# GPS_module.net
KiCad netlist of a schematic drawn in EAGLE
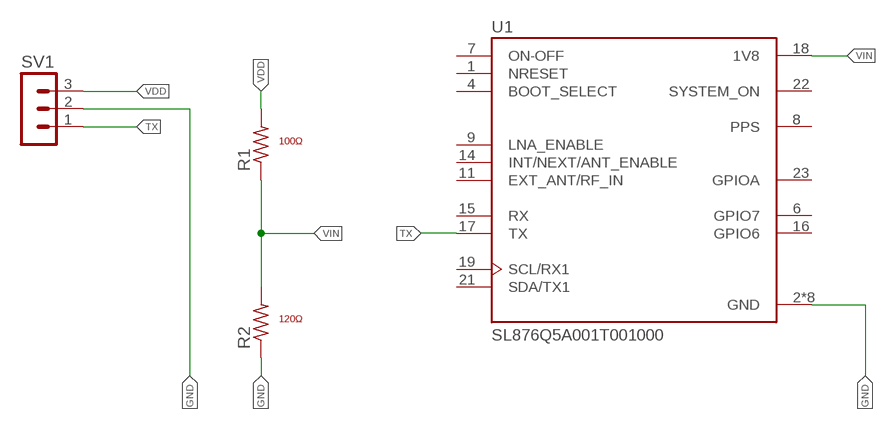
[diagram p0: schematic, sheet 1]

(export (version "E")
  (design (tool "Eeschema 10.0.6"))
  (components
    (comp (ref "R1")
      (value "100")
      (footprint "eagle-import:RESC2012X65N")
      (fields
        (field (name "COMMENT") "1623401-1")
        (field (name "MF") "TE Connectivity")
        (field (name "TOLERANCE") "0%")
      )
      (libsource (lib "eagle-import") (part "1623401-1"))
    )
    (comp (ref "R2")
      (value "120")
      (footprint "eagle-import:RESC2012X65N")
      (fields
        (field (name "COMMENT") "1623401-1")
        (field (name "MF") "TE Connectivity")
        (field (name "TOLERANCE") "0%")
      )
      (libsource (lib "eagle-import") (part "1623401-1"))
    )
    (comp (ref "SV1")
      (value "MA03-1")
      (footprint "eagle-import:MA03-1")
      (libsource (lib "eagle-import") (part "MA03-1"))
    )
    (comp (ref "U1")
      (value "SL876Q5A001T001000")
      (footprint "eagle-import:XCVR_SL876Q5A001T001000")
      (fields (field (name "MF") "Telit"))
      (libsource (lib "eagle-import") (part "SL876Q5A001T001000"))
    )
  )
  (nets
    (net (code "1") (name "GND") (class "Default")
      (node (ref "R2") (pin "1") (pinfunction "1_1") (pintype "passive"))
      (node (ref "SV1") (pin "2") (pinfunction "2_2") (pintype "passive"))
      (node (ref "U1") (pin "10") (pinfunction "GND_10") (pintype "power_in"))
      (node (ref "U1") (pin "12") (pinfunction "GND_12") (pintype "power_in"))
      (node (ref "U1") (pin "13") (pinfunction "GND_13") (pintype "power_in"))
      (node (ref "U1") (pin "2") (pinfunction "GND_2") (pintype "power_in"))
      (node (ref "U1") (pin "20") (pinfunction "GND_20") (pintype "power_in"))
      (node (ref "U1") (pin "24") (pinfunction "GND_24") (pintype "power_in"))
      (node (ref "U1") (pin "3") (pinfunction "GND_3") (pintype "power_in"))
      (node (ref "U1") (pin "5") (pinfunction "GND_5") (pintype "power_in"))
    )
    (net (code "2") (name "TX") (class "Default")
      (node (ref "SV1") (pin "1") (pinfunction "1_1") (pintype "passive"))
      (node (ref "U1") (pin "17") (pinfunction "TX_17") (pintype "output"))
    )
    (net (code "3") (name "VDD") (class "Default")
      (node (ref "R1") (pin "2") (pinfunction "2_2") (pintype "passive"))
      (node (ref "SV1") (pin "3") (pinfunction "3_3") (pintype "passive"))
    )
    (net (code "4") (name "VIN") (class "Default")
      (node (ref "R1") (pin "1") (pinfunction "1_1") (pintype "passive"))
      (node (ref "R2") (pin "2") (pinfunction "2_2") (pintype "passive"))
      (node (ref "U1") (pin "18") (pinfunction "1V8_18") (pintype "power_in"))
    )
    (net (code "5") (name "unconnected-(U1-BOOT_SELECT-Pad4)") (class "Default")
      (node (ref "U1") (pin "4") (pinfunction "BOOT_SELECT_4") (pintype "input"))
    )
    (net (code "6") (name "unconnected-(U1-EXT_ANT{slash}RF_IN-Pad11)") (class "Default")
      (node (ref "U1") (pin "11") (pinfunction "EXT_ANT/RF_IN_11") (pintype "input"))
    )
    (net (code "7") (name "unconnected-(U1-GPIO6-Pad16)") (class "Default")
      (node (ref "U1") (pin "16") (pinfunction "GPIO6_16") (pintype "bidirectional"))
    )
    (net (code "8") (name "unconnected-(U1-GPIO7-Pad6)") (class "Default")
      (node (ref "U1") (pin "6") (pinfunction "GPIO7_6") (pintype "bidirectional"))
    )
    (net (code "9") (name "unconnected-(U1-GPIOA-Pad23)") (class "Default")
      (node (ref "U1") (pin "23") (pinfunction "GPIOA_23") (pintype "output"))
    )
    (net (code "10") (name "unconnected-(U1-INT{slash}NEXT{slash}ANT_ENABLE-Pad14)") (class "Default")
      (node (ref "U1") (pin "14") (pinfunction "INT/NEXT/ANT_ENABLE_14") (pintype "input"))
    )
    (net (code "11") (name "unconnected-(U1-LNA_ENABLE-Pad9)") (class "Default")
      (node (ref "U1") (pin "9") (pinfunction "LNA_ENABLE_9") (pintype "output"))
    )
    (net (code "12") (name "unconnected-(U1-NRESET-Pad1)") (class "Default")
      (node (ref "U1") (pin "1") (pinfunction "NRESET_1") (pintype "input"))
    )
    (net (code "13") (name "unconnected-(U1-ON-OFF-Pad7)") (class "Default")
      (node (ref "U1") (pin "7") (pinfunction "ON-OFF_7") (pintype "input"))
    )
    (net (code "14") (name "unconnected-(U1-PPS-Pad8)") (class "Default")
      (node (ref "U1") (pin "8") (pinfunction "PPS_8") (pintype "output"))
    )
    (net (code "15") (name "unconnected-(U1-RX-Pad15)") (class "Default")
      (node (ref "U1") (pin "15") (pinfunction "RX_15") (pintype "input"))
    )
    (net (code "16") (name "unconnected-(U1-SCL{slash}RX1-Pad19)") (class "Default")
      (node (ref "U1") (pin "19") (pinfunction "SCL/RX1_19") (pintype "bidirectional"))
    )
    (net (code "17") (name "unconnected-(U1-SDA{slash}TX1-Pad21)") (class "Default")
      (node (ref "U1") (pin "21") (pinfunction "SDA/TX1_21") (pintype "bidirectional"))
    )
    (net (code "18") (name "unconnected-(U1-SYSTEM_ON-Pad22)") (class "Default")
      (node (ref "U1") (pin "22") (pinfunction "SYSTEM_ON_22") (pintype "output"))
    )
  )
)
